# Envelopekut.net
KiCad netlist of a schematic drawn in EAGLE
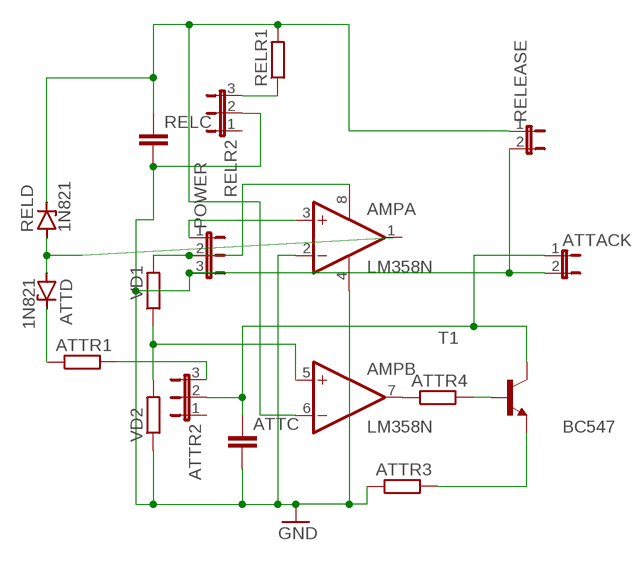
[diagram p0: schematic, sheet 1]

(export (version "E")
  (design (tool "Eeschema 10.0.6"))
  (components
    (comp (ref "AMP")
      (value "LM358N")
      (footprint "eagle-import:DIL08")
      (libsource (lib "eagle-import") (part "LM358N"))
    )
    (comp (ref "ATTACK")
      (value "JP1E")
      (footprint "eagle-import:JP1")
      (libsource (lib "eagle-import") (part "JP1E"))
    )
    (comp (ref "ATTC")
      (value "C-EU025-025X050")
      (footprint "eagle-import:C025-025X050")
      (libsource (lib "eagle-import") (part "C-EU025-025X050"))
    )
    (comp (ref "ATTD")
      (value "1N821")
      (footprint "eagle-import:DO35Z10")
      (libsource (lib "eagle-import") (part "1N821"))
    )
    (comp (ref "ATTR1")
      (value "R-EU_0207/10")
      (footprint "eagle-import:0207_10")
      (libsource (lib "eagle-import") (part "R-EU_0207/10"))
    )
    (comp (ref "ATTR2")
      (value "JP2E")
      (footprint "eagle-import:JP2")
      (libsource (lib "eagle-import") (part "JP2E"))
    )
    (comp (ref "ATTR3")
      (value "R-EU_0207/10")
      (footprint "eagle-import:0207_10")
      (libsource (lib "eagle-import") (part "R-EU_0207/10"))
    )
    (comp (ref "ATTR4")
      (value "R-EU_0207/10")
      (footprint "eagle-import:0207_10")
      (libsource (lib "eagle-import") (part "R-EU_0207/10"))
    )
    (comp (ref "POWER")
      (value "JP2E")
      (footprint "eagle-import:JP2")
      (libsource (lib "eagle-import") (part "JP2E"))
    )
    (comp (ref "RELC")
      (value "C-EU025-025X050")
      (footprint "eagle-import:C025-025X050")
      (libsource (lib "eagle-import") (part "C-EU025-025X050"))
    )
    (comp (ref "RELD")
      (value "1N821")
      (footprint "eagle-import:DO35Z10")
      (libsource (lib "eagle-import") (part "1N821"))
    )
    (comp (ref "RELEASE")
      (value "JP1E")
      (footprint "eagle-import:JP1")
      (libsource (lib "eagle-import") (part "JP1E"))
    )
    (comp (ref "RELR1")
      (value "R-EU_0207/10")
      (footprint "eagle-import:0207_10")
      (libsource (lib "eagle-import") (part "R-EU_0207/10"))
    )
    (comp (ref "RELR2")
      (value "JP2E")
      (footprint "eagle-import:JP2")
      (libsource (lib "eagle-import") (part "JP2E"))
    )
    (comp (ref "T1")
      (value "BC547")
      (footprint "eagle-import:TO92")
      (libsource (lib "eagle-import") (part "BC547"))
    )
    (comp (ref "VD1")
      (value "R-EU_0207/10")
      (footprint "eagle-import:0207_10")
      (libsource (lib "eagle-import") (part "R-EU_0207/10"))
    )
    (comp (ref "VD2")
      (value "R-EU_0207/10")
      (footprint "eagle-import:0207_10")
      (libsource (lib "eagle-import") (part "R-EU_0207/10"))
    )
  )
  (nets
    (net (code "1") (name "GND") (class "Default")
      (node (ref "AMP") (pin "2") (pinfunction "-IN_2") (pintype "input"))
      (node (ref "AMP") (pin "4") (pinfunction "V-_4") (pintype "power_in"))
      (node (ref "ATTACK") (pin "2") (pinfunction "2_2") (pintype "passive"))
      (node (ref "ATTC") (pin "2") (pinfunction "2_2") (pintype "passive"))
      (node (ref "ATTR3") (pin "1") (pinfunction "1_1") (pintype "passive"))
      (node (ref "POWER") (pin "3") (pinfunction "3_3") (pintype "passive"))
      (node (ref "RELC") (pin "2") (pinfunction "2_2") (pintype "passive"))
      (node (ref "RELEASE") (pin "2") (pinfunction "2_2") (pintype "passive"))
      (node (ref "RELR2") (pin "2") (pinfunction "2_2") (pintype "passive"))
      (node (ref "VD2") (pin "1") (pinfunction "1_1") (pintype "passive"))
    )
    (net (code "2") (name "Net-(AMPA-+IN)") (class "Default")
      (node (ref "AMP") (pin "3") (pinfunction "+IN_3") (pintype "input"))
      (node (ref "POWER") (pin "1") (pinfunction "1_1") (pintype "passive"))
    )
    (net (code "3") (name "Net-(AMPA-OUT)") (class "Default")
      (node (ref "AMP") (pin "1") (pinfunction "OUT_1") (pintype "output"))
      (node (ref "ATTD") (pin "A") (pinfunction "A_A") (pintype "passive"))
      (node (ref "RELD") (pin "A") (pinfunction "A_A") (pintype "passive"))
    )
    (net (code "4") (name "Net-(AMPB-+IN)") (class "Default")
      (node (ref "AMP") (pin "5") (pinfunction "+IN_5") (pintype "input"))
      (node (ref "VD1") (pin "1") (pinfunction "1_1") (pintype "passive"))
      (node (ref "VD2") (pin "2") (pinfunction "2_2") (pintype "passive"))
    )
    (net (code "5") (name "Net-(AMPB--IN)") (class "Default")
      (node (ref "AMP") (pin "6") (pinfunction "-IN_6") (pintype "input"))
      (node (ref "RELC") (pin "1") (pinfunction "1_1") (pintype "passive"))
      (node (ref "RELD") (pin "C") (pinfunction "C_C") (pintype "passive"))
      (node (ref "RELEASE") (pin "1") (pinfunction "1_1") (pintype "passive"))
      (node (ref "RELR1") (pin "2") (pinfunction "2_2") (pintype "passive"))
    )
    (net (code "6") (name "Net-(AMPB-OUT)") (class "Default")
      (node (ref "AMP") (pin "7") (pinfunction "OUT_7") (pintype "output"))
      (node (ref "ATTR4") (pin "1") (pinfunction "1_1") (pintype "passive"))
    )
    (net (code "7") (name "Net-(AMPC-V+)") (class "Default")
      (node (ref "AMP") (pin "8") (pinfunction "V+_8") (pintype "power_in"))
      (node (ref "POWER") (pin "2") (pinfunction "2_2") (pintype "passive"))
      (node (ref "VD1") (pin "2") (pinfunction "2_2") (pintype "passive"))
    )
    (net (code "8") (name "Net-(ATTD-PadC)") (class "Default")
      (node (ref "ATTD") (pin "C") (pinfunction "C_C") (pintype "passive"))
      (node (ref "ATTR1") (pin "1") (pinfunction "1_1") (pintype "passive"))
    )
    (net (code "9") (name "Net-(ATTR1-Pad2)") (class "Default")
      (node (ref "ATTR1") (pin "2") (pinfunction "2_2") (pintype "passive"))
      (node (ref "ATTR2") (pin "3") (pinfunction "3_3") (pintype "passive"))
    )
    (net (code "10") (name "Net-(RELR1-Pad1)") (class "Default")
      (node (ref "RELR1") (pin "1") (pinfunction "1_1") (pintype "passive"))
      (node (ref "RELR2") (pin "3") (pinfunction "3_3") (pintype "passive"))
    )
    (net (code "11") (name "Net-(T1-B)") (class "Default")
      (node (ref "ATTR4") (pin "2") (pinfunction "2_2") (pintype "passive"))
      (node (ref "T1") (pin "2") (pinfunction "B_2") (pintype "passive"))
    )
    (net (code "12") (name "Net-(T1-C)") (class "Default")
      (node (ref "ATTACK") (pin "1") (pinfunction "1_1") (pintype "passive"))
      (node (ref "ATTC") (pin "1") (pinfunction "1_1") (pintype "passive"))
      (node (ref "ATTR2") (pin "2") (pinfunction "2_2") (pintype "passive"))
      (node (ref "T1") (pin "3") (pinfunction "C_3") (pintype "passive"))
    )
    (net (code "13") (name "Net-(T1-E)") (class "Default")
      (node (ref "ATTR3") (pin "2") (pinfunction "2_2") (pintype "passive"))
      (node (ref "T1") (pin "1") (pinfunction "E_1") (pintype "passive"))
    )
    (net (code "14") (name "unconnected-(ATTR2-Pad1)") (class "Default")
      (node (ref "ATTR2") (pin "1") (pinfunction "1_1") (pintype "passive"))
    )
    (net (code "15") (name "unconnected-(RELR2-Pad1)") (class "Default")
      (node (ref "RELR2") (pin "1") (pinfunction "1_1") (pintype "passive"))
    )
  )
)
